# Relay.net
KiCad netlist of a schematic drawn in Altium Designer
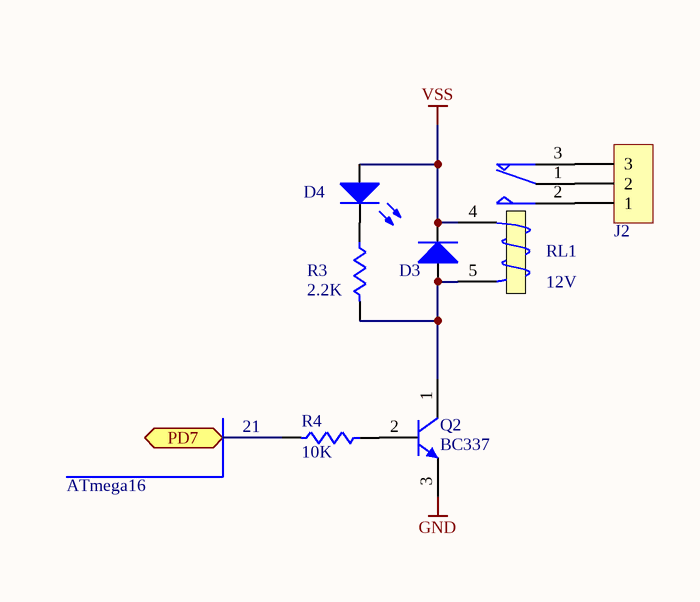
[diagram p0: Relay.SchDoc]

(export (version "E")
  (design (tool "Eeschema 10.0.6"))
  (components
    (comp (ref "D3")
      (value "Diode")
      (footprint "DIODE0.35")
      (fields (field (name "MANUFACTURER") "Generic Components") (field (name "PUBLISHER") "Altium Limited"))
      (libsource (lib "my Libraries") (part "Diode"))
    )
    (comp (ref "D4")
      (value "Optical Transmitter")
      (footprint "LED_5mm")
      (description "Typical INFRARED GaAs LED")
      (fields (field (name "MANUFACTURER") "Generic Components") (field (name "PUBLISHER") "Altium Limited"))
      (libsource (lib "my Libraries") (part "Optical Transmitter"))
    )
    (comp (ref "J2")
      (value "Connector_3pin")
      (footprint "Fonics_3C")
      (description "Header, 3-Pin")
      (fields (field (name "MANUFACTURER") "Generic Components") (field (name "PUBLISHER") "Altium Limited"))
      (libsource (lib "my Libraries") (part "Connector_3pin"))
    )
    (comp (ref "Q2")
      (value "NPN")
      (footprint "TO92C")
      (description "Silicon Bipolar Transistor")
      (fields (field (name "DEVICE") "BC337"))
      (libsource (lib "my Libraries") (part "NPN"))
    )
    (comp (ref "R3")
      (value "2.2K")
      (footprint "AXIAL0.4")
      (description "Resistor")
      (fields (field (name "MANUFACTURER") "Generic Components") (field (name "PUBLISHER") "Altium Limited"))
      (libsource (lib "my Libraries") (part "Resistor"))
    )
    (comp (ref "R4")
      (value "10K")
      (footprint "AXIAL0.4")
      (description "Resistor")
      (fields (field (name "MANUFACTURER") "Generic Components") (field (name "PUBLISHER") "Altium Limited"))
      (libsource (lib "my Libraries") (part "Resistor"))
    )
    (comp (ref "RL1")
      (value "12V")
      (footprint "RELAY-SPDT-1")
      (description "SPDT Relay")
      (fields
        (field (name "MANUFACTURER") "Generic Components")
        (field (name "Comment") "Relay_SPDT")
        (field (name "PUBLISHER") "Altium Limited")
      )
      (libsource (lib "my Libraries") (part "Relay_SPDT"))
    )
  )
  (nets
    (net (code "1") (name "/PD7") (class "Default")
      (node (ref "R4") (pin "2") (pinfunction "2_2") (pintype "passive"))
    )
    (net (code "2") (name "GND") (class "Default")
      (node (ref "Q2") (pin "3") (pinfunction "E_3") (pintype "passive"))
    )
    (net (code "3") (name "Net-(D3-A)") (class "Default")
      (node (ref "D3") (pin "1") (pinfunction "A_1") (pintype "passive"))
      (node (ref "Q2") (pin "1") (pinfunction "C_1") (pintype "passive"))
      (node (ref "R3") (pin "2") (pinfunction "2_2") (pintype "passive"))
      (node (ref "RL1") (pin "5") (pinfunction "T2_5") (pintype "passive"))
    )
    (net (code "4") (name "Net-(D4-K)") (class "Default")
      (node (ref "D4") (pin "2") (pinfunction "K_2") (pintype "passive"))
      (node (ref "R3") (pin "1") (pinfunction "1_1") (pintype "passive"))
    )
    (net (code "5") (name "Net-(Q2-B)") (class "Default")
      (node (ref "Q2") (pin "2") (pinfunction "B_2") (pintype "passive"))
      (node (ref "R4") (pin "1") (pinfunction "1_1") (pintype "passive"))
    )
    (net (code "6") (name "Net-(RL1-COM)") (class "Default")
      (node (ref "J2") (pin "2") (pinfunction "2_2") (pintype "passive"))
      (node (ref "RL1") (pin "1") (pinfunction "COM_1") (pintype "passive"))
    )
    (net (code "7") (name "Net-(RL1-NC)") (class "Default")
      (node (ref "J2") (pin "3") (pinfunction "3_3") (pintype "passive"))
      (node (ref "RL1") (pin "3") (pinfunction "NC_3") (pintype "passive"))
    )
    (net (code "8") (name "Net-(RL1-NO)") (class "Default")
      (node (ref "J2") (pin "1") (pinfunction "1_1") (pintype "passive"))
      (node (ref "RL1") (pin "2") (pinfunction "NO_2") (pintype "passive"))
    )
    (net (code "9") (name "VSS") (class "Default")
      (node (ref "D3") (pin "2") (pinfunction "K_2") (pintype "passive"))
      (node (ref "D4") (pin "1") (pinfunction "A_1") (pintype "passive"))
      (node (ref "RL1") (pin "4") (pinfunction "T1_4") (pintype "passive"))
    )
  )
)
